# ComboBreaker.net
KiCad netlist of a schematic drawn in EAGLE
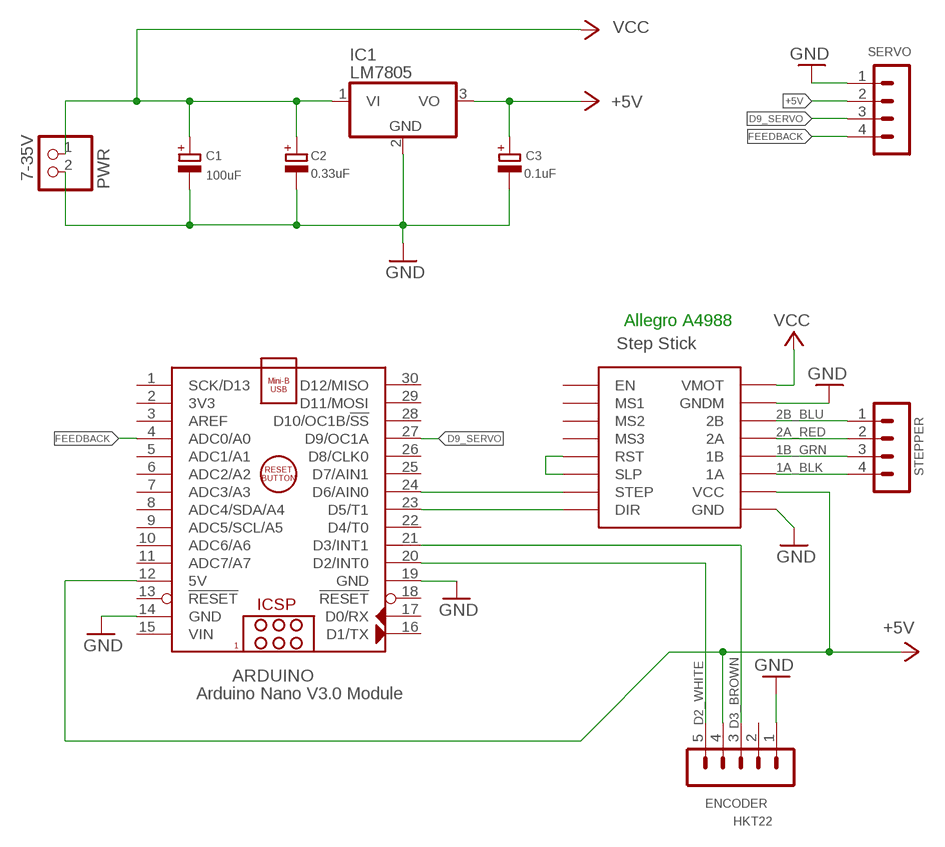
[diagram p0: schematic, sheet 1]

(export (version "E")
  (design (tool "Eeschema 10.0.6"))
  (components
    (comp (ref "ARDUINO")
      (value "Arduino Nano V3.0 Module")
      (footprint "eagle-import:ARDUINO_NANO")
      (libsource (lib "eagle-import") (part "ARDUINO_NANO"))
    )
    (comp (ref "C1")
      (value "100uF")
      (footprint "eagle-import:E2-4")
      (libsource (lib "eagle-import") (part "CPOL-EUE2-4"))
    )
    (comp (ref "C2")
      (value "0.33uF")
      (footprint "eagle-import:E2-4")
      (libsource (lib "eagle-import") (part "CPOL-EUE2-4"))
    )
    (comp (ref "C3")
      (value "0.1uF")
      (footprint "eagle-import:E2-4")
      (libsource (lib "eagle-import") (part "CPOL-EUE2-4"))
    )
    (comp (ref "ENCODER")
      (value "HKT22")
      (footprint "eagle-import:MA05-1")
      (libsource (lib "eagle-import") (part "MA05-1"))
    )
    (comp (ref "IC1")
      (value "LM7805")
      (footprint "eagle-import:TO220V")
      (libsource (lib "eagle-import") (part "78TV05"))
    )
    (comp (ref "PWR")
      (value "7-35V")
      (footprint "eagle-import:JST-PH-2-SMT")
      (libsource (lib "eagle-import") (part "JST_2PIN-SMT"))
    )
    (comp (ref "SERVO")
      (value "MA04-1")
      (footprint "eagle-import:MA04-1")
      (libsource (lib "eagle-import") (part "MA04-1"))
    )
    (comp (ref "STEPPER")
      (value "MA04-1")
      (footprint "eagle-import:MA04-1")
      (libsource (lib "eagle-import") (part "MA04-1"))
    )
    (comp (ref "U$2")
      (value "Allegro A4988")
      (footprint "eagle-import:STEP-STICK")
      (libsource (lib "eagle-import") (part "STEP-STICK"))
    )
  )
  (nets
    (net (code "1") (name "+5V") (class "Default")
      (node (ref "ARDUINO") (pin "12") (pinfunction "5V_12") (pintype "power_in"))
      (node (ref "C3") (pin "+") (pinfunction "+_+") (pintype "passive"))
      (node (ref "ENCODER") (pin "4") (pinfunction "4_4") (pintype "passive"))
      (node (ref "IC1") (pin "3") (pinfunction "VO_3") (pintype "passive"))
      (node (ref "SERVO") (pin "2") (pinfunction "2_2") (pintype "passive"))
      (node (ref "U$2") (pin "VCC") (pinfunction "VCC_VCC") (pintype "bidirectional"))
    )
    (net (code "2") (name "/1A_BLK") (class "Default")
      (node (ref "STEPPER") (pin "4") (pinfunction "4_4") (pintype "passive"))
      (node (ref "U$2") (pin "1A") (pinfunction "1A_1A") (pintype "bidirectional"))
    )
    (net (code "3") (name "/1B_GRN") (class "Default")
      (node (ref "STEPPER") (pin "3") (pinfunction "3_3") (pintype "passive"))
      (node (ref "U$2") (pin "1B") (pinfunction "1B_1B") (pintype "bidirectional"))
    )
    (net (code "4") (name "/2A_RED") (class "Default")
      (node (ref "STEPPER") (pin "2") (pinfunction "2_2") (pintype "passive"))
      (node (ref "U$2") (pin "2A") (pinfunction "2A_2A") (pintype "bidirectional"))
    )
    (net (code "5") (name "/2B_BLU") (class "Default")
      (node (ref "STEPPER") (pin "1") (pinfunction "1_1") (pintype "passive"))
      (node (ref "U$2") (pin "2B") (pinfunction "2B_2B") (pintype "bidirectional"))
    )
    (net (code "6") (name "/D2_WHITE") (class "Default")
      (node (ref "ARDUINO") (pin "20") (pinfunction "D2/INT0_20") (pintype "bidirectional"))
      (node (ref "ENCODER") (pin "5") (pinfunction "5_5") (pintype "passive"))
    )
    (net (code "7") (name "/D3_BROWN") (class "Default")
      (node (ref "ARDUINO") (pin "21") (pinfunction "D3/INT1_21") (pintype "bidirectional"))
      (node (ref "ENCODER") (pin "3") (pinfunction "3_3") (pintype "passive"))
    )
    (net (code "8") (name "/VIN") (class "Default")
      (node (ref "ARDUINO") (pin "15") (pinfunction "VIN_15") (pintype "power_in"))
    )
    (net (code "9") (name "D9_SERVO") (class "Default")
      (node (ref "ARDUINO") (pin "27") (pinfunction "D9/OC1A_27") (pintype "bidirectional"))
      (node (ref "SERVO") (pin "3") (pinfunction "3_3") (pintype "passive"))
    )
    (net (code "10") (name "FEEDBACK") (class "Default")
      (node (ref "ARDUINO") (pin "4") (pinfunction "ADC0/A0_4") (pintype "bidirectional"))
      (node (ref "SERVO") (pin "4") (pinfunction "4_4") (pintype "passive"))
    )
    (net (code "11") (name "GND") (class "Default")
      (node (ref "ARDUINO") (pin "14") (pinfunction "GND_14") (pintype "power_in"))
      (node (ref "ARDUINO") (pin "19") (pinfunction "GND_19") (pintype "power_in"))
      (node (ref "C1") (pin "-") (pinfunction "-_-") (pintype "passive"))
      (node (ref "C2") (pin "-") (pinfunction "-_-") (pintype "passive"))
      (node (ref "C3") (pin "-") (pinfunction "-_-") (pintype "passive"))
      (node (ref "ENCODER") (pin "1") (pinfunction "1_1") (pintype "passive"))
      (node (ref "IC1") (pin "2") (pinfunction "GND_2") (pintype "passive"))
      (node (ref "PWR") (pin "2") (pinfunction "1_2") (pintype "passive"))
      (node (ref "SERVO") (pin "1") (pinfunction "1_1") (pintype "passive"))
      (node (ref "U$2") (pin "GND") (pinfunction "GND_GND") (pintype "bidirectional"))
      (node (ref "U$2") (pin "GNDM") (pinfunction "GNDM_GNDM") (pintype "bidirectional"))
    )
    (net (code "12") (name "Net-(ARDUINO-D5{slash}T1)") (class "Default")
      (node (ref "ARDUINO") (pin "23") (pinfunction "D5/T1_23") (pintype "bidirectional"))
      (node (ref "U$2") (pin "DIR") (pinfunction "DIR_DIR") (pintype "bidirectional"))
    )
    (net (code "13") (name "Net-(ARDUINO-D6{slash}AIN0)") (class "Default")
      (node (ref "ARDUINO") (pin "24") (pinfunction "D6/AIN0_24") (pintype "bidirectional"))
      (node (ref "U$2") (pin "SPT") (pinfunction "STEP_SPT") (pintype "bidirectional"))
    )
    (net (code "14") (name "Net-(U$2-PadRST)") (class "Default")
      (node (ref "U$2") (pin "RST") (pinfunction "RST_RST") (pintype "bidirectional"))
      (node (ref "U$2") (pin "SLP") (pinfunction "SLP_SLP") (pintype "bidirectional"))
    )
    (net (code "15") (name "VCC") (class "Default")
      (node (ref "C1") (pin "+") (pinfunction "+_+") (pintype "passive"))
      (node (ref "C2") (pin "+") (pinfunction "+_+") (pintype "passive"))
      (node (ref "IC1") (pin "1") (pinfunction "VI_1") (pintype "input"))
      (node (ref "PWR") (pin "1") (pinfunction "2_1") (pintype "passive"))
      (node (ref "U$2") (pin "VMOT") (pinfunction "VMOT_VMOT") (pintype "bidirectional"))
    )
    (net (code "16") (name "unconnected-(ARDUINO-3V3-Pad2)") (class "Default")
      (node (ref "ARDUINO") (pin "2") (pinfunction "3V3_2") (pintype "output"))
    )
    (net (code "17") (name "unconnected-(ARDUINO-ADC1{slash}A1-Pad5)") (class "Default")
      (node (ref "ARDUINO") (pin "5") (pinfunction "ADC1/A1_5") (pintype "bidirectional"))
    )
    (net (code "18") (name "unconnected-(ARDUINO-ADC2{slash}A2-Pad6)") (class "Default")
      (node (ref "ARDUINO") (pin "6") (pinfunction "ADC2/A2_6") (pintype "bidirectional"))
    )
    (net (code "19") (name "unconnected-(ARDUINO-ADC3{slash}A3-Pad7)") (class "Default")
      (node (ref "ARDUINO") (pin "7") (pinfunction "ADC3/A3_7") (pintype "bidirectional"))
    )
    (net (code "20") (name "unconnected-(ARDUINO-ADC4{slash}SDA{slash}A4-Pad8)") (class "Default")
      (node (ref "ARDUINO") (pin "8") (pinfunction "ADC4/SDA/A4_8") (pintype "bidirectional"))
    )
    (net (code "21") (name "unconnected-(ARDUINO-ADC5{slash}SCL{slash}A5-Pad9)") (class "Default")
      (node (ref "ARDUINO") (pin "9") (pinfunction "ADC5/SCL/A5_9") (pintype "bidirectional"))
    )
    (net (code "22") (name "unconnected-(ARDUINO-ADC6{slash}A6-Pad10)") (class "Default")
      (node (ref "ARDUINO") (pin "10") (pinfunction "ADC6/A6_10") (pintype "bidirectional"))
    )
    (net (code "23") (name "unconnected-(ARDUINO-ADC7{slash}A7-Pad11)") (class "Default")
      (node (ref "ARDUINO") (pin "11") (pinfunction "ADC7/A7_11") (pintype "bidirectional"))
    )
    (net (code "24") (name "unconnected-(ARDUINO-AREF-Pad3)") (class "Default")
      (node (ref "ARDUINO") (pin "3") (pinfunction "AREF_3") (pintype "input"))
    )
    (net (code "25") (name "unconnected-(ARDUINO-D0{slash}RX-Pad17)") (class "Default")
      (node (ref "ARDUINO") (pin "17") (pinfunction "D0/RX_17") (pintype "bidirectional"))
    )
    (net (code "26") (name "unconnected-(ARDUINO-D1{slash}TX-Pad16)") (class "Default")
      (node (ref "ARDUINO") (pin "16") (pinfunction "D1/TX_16") (pintype "bidirectional"))
    )
    (net (code "27") (name "unconnected-(ARDUINO-D4{slash}T0-Pad22)") (class "Default")
      (node (ref "ARDUINO") (pin "22") (pinfunction "D4/T0_22") (pintype "bidirectional"))
    )
    (net (code "28") (name "unconnected-(ARDUINO-D7{slash}AIN1-Pad25)") (class "Default")
      (node (ref "ARDUINO") (pin "25") (pinfunction "D7/AIN1_25") (pintype "bidirectional"))
    )
    (net (code "29") (name "unconnected-(ARDUINO-D8{slash}CLK0-Pad26)") (class "Default")
      (node (ref "ARDUINO") (pin "26") (pinfunction "D8/CLK0_26") (pintype "bidirectional"))
    )
    (net (code "30") (name "unconnected-(ARDUINO-D10{slash}OC1B{slash}~{SS}-Pad28)") (class "Default")
      (node (ref "ARDUINO") (pin "28") (pinfunction "D10/OC1B/~{SS}_28") (pintype "bidirectional"))
    )
    (net (code "31") (name "unconnected-(ARDUINO-D11{slash}MOSI-Pad29)") (class "Default")
      (node (ref "ARDUINO") (pin "29") (pinfunction "D11/MOSI_29") (pintype "bidirectional"))
    )
    (net (code "32") (name "unconnected-(ARDUINO-D12{slash}MISO-Pad30)") (class "Default")
      (node (ref "ARDUINO") (pin "30") (pinfunction "D12/MISO_30") (pintype "bidirectional"))
    )
    (net (code "33") (name "unconnected-(ARDUINO-SCK{slash}D13-Pad1)") (class "Default")
      (node (ref "ARDUINO") (pin "1") (pinfunction "SCK/D13_1") (pintype "bidirectional"))
    )
    (net (code "34") (name "unconnected-(ARDUINO-~{RESET}-Pad13)") (class "Default")
      (node (ref "ARDUINO") (pin "13") (pinfunction "~{RESET}_13") (pintype "input"))
    )
    (net (code "35") (name "unconnected-(ARDUINO-~{RESET}-Pad18)") (class "Default")
      (node (ref "ARDUINO") (pin "18") (pinfunction "~{RESET}_18") (pintype "input"))
    )
    (net (code "36") (name "unconnected-(ENCODER-Pad2)") (class "Default")
      (node (ref "ENCODER") (pin "2") (pinfunction "2_2") (pintype "passive"))
    )
    (net (code "37") (name "unconnected-(U$2-PadEN)") (class "Default")
      (node (ref "U$2") (pin "EN") (pinfunction "EN_EN") (pintype "bidirectional"))
    )
    (net (code "38") (name "unconnected-(U$2-PadMS1)") (class "Default")
      (node (ref "U$2") (pin "MS1") (pinfunction "MS1_MS1") (pintype "bidirectional"))
    )
    (net (code "39") (name "unconnected-(U$2-PadMS2)") (class "Default")
      (node (ref "U$2") (pin "MS2") (pinfunction "MS2_MS2") (pintype "bidirectional"))
    )
    (net (code "40") (name "unconnected-(U$2-PadMS3)") (class "Default")
      (node (ref "U$2") (pin "MS3") (pinfunction "MS3_MS3") (pintype "bidirectional"))
    )
  )
)
